# info.net
KiCad netlist of a schematic drawn in EAGLE
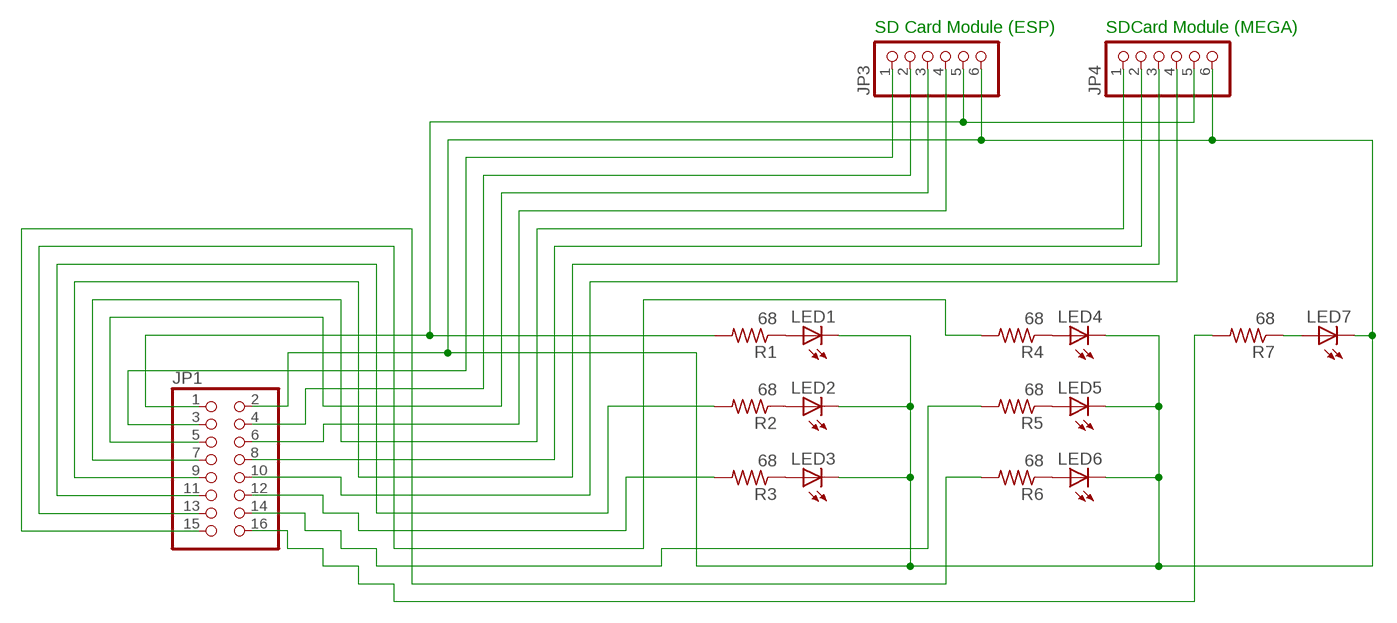
[diagram p0: schematic, sheet 1]

(export (version "E")
  (design (tool "Eeschema 10.0.6"))
  (components
    (comp (ref "JP1")
      (value "PINHD-2X8/90")
      (footprint "eagle-import:2X08_90")
      (libsource (lib "eagle-import") (part "PINHD-2X8/90"))
    )
    (comp (ref "JP3")
      (value "PINHD-1X6")
      (footprint "eagle-import:1X06")
      (libsource (lib "eagle-import") (part "PINHD-1X6"))
    )
    (comp (ref "JP4")
      (value "PINHD-1X6")
      (footprint "eagle-import:1X06")
      (libsource (lib "eagle-import") (part "PINHD-1X6"))
    )
    (comp (ref "LED1")
      (value "LED3MM")
      (footprint "eagle-import:LED3MM")
      (libsource (lib "eagle-import") (part "LED3MM"))
    )
    (comp (ref "LED2")
      (value "LED3MM")
      (footprint "eagle-import:LED3MM")
      (libsource (lib "eagle-import") (part "LED3MM"))
    )
    (comp (ref "LED3")
      (value "LED3MM")
      (footprint "eagle-import:LED3MM")
      (libsource (lib "eagle-import") (part "LED3MM"))
    )
    (comp (ref "LED4")
      (value "LED3MM")
      (footprint "eagle-import:LED3MM")
      (libsource (lib "eagle-import") (part "LED3MM"))
    )
    (comp (ref "LED5")
      (value "LED3MM")
      (footprint "eagle-import:LED3MM")
      (libsource (lib "eagle-import") (part "LED3MM"))
    )
    (comp (ref "LED6")
      (value "LED3MM")
      (footprint "eagle-import:LED3MM")
      (libsource (lib "eagle-import") (part "LED3MM"))
    )
    (comp (ref "LED7")
      (value "LED3MM")
      (footprint "eagle-import:LED3MM")
      (libsource (lib "eagle-import") (part "LED3MM"))
    )
    (comp (ref "R1")
      (value "68")
      (footprint "eagle-import:0204_7")
      (libsource (lib "eagle-import") (part "R-US_0204/7"))
    )
    (comp (ref "R2")
      (value "68")
      (footprint "eagle-import:0204_7")
      (libsource (lib "eagle-import") (part "R-US_0204/7"))
    )
    (comp (ref "R3")
      (value "68")
      (footprint "eagle-import:0204_7")
      (libsource (lib "eagle-import") (part "R-US_0204/7"))
    )
    (comp (ref "R4")
      (value "68")
      (footprint "eagle-import:0204_7")
      (libsource (lib "eagle-import") (part "R-US_0204/7"))
    )
    (comp (ref "R5")
      (value "68")
      (footprint "eagle-import:0204_7")
      (libsource (lib "eagle-import") (part "R-US_0204/7"))
    )
    (comp (ref "R6")
      (value "68")
      (footprint "eagle-import:0204_7")
      (libsource (lib "eagle-import") (part "R-US_0204/7"))
    )
    (comp (ref "R7")
      (value "68")
      (footprint "eagle-import:0204_7")
      (libsource (lib "eagle-import") (part "R-US_0204/7"))
    )
  )
  (nets
    (net (code "1") (name "Net-(JP1-Pad1)") (class "Default")
      (node (ref "JP1") (pin "1") (pinfunction "1_1") (pintype "passive"))
      (node (ref "JP3") (pin "5") (pinfunction "5_5") (pintype "passive"))
      (node (ref "JP4") (pin "5") (pinfunction "5_5") (pintype "passive"))
      (node (ref "R1") (pin "2") (pinfunction "2_2") (pintype "passive"))
    )
    (net (code "2") (name "Net-(JP1-Pad3)") (class "Default")
      (node (ref "JP1") (pin "3") (pinfunction "3_3") (pintype "passive"))
      (node (ref "JP3") (pin "1") (pinfunction "1_1") (pintype "passive"))
    )
    (net (code "3") (name "Net-(JP1-Pad4)") (class "Default")
      (node (ref "JP1") (pin "4") (pinfunction "4_4") (pintype "passive"))
      (node (ref "JP3") (pin "2") (pinfunction "2_2") (pintype "passive"))
    )
    (net (code "4") (name "Net-(JP1-Pad5)") (class "Default")
      (node (ref "JP1") (pin "5") (pinfunction "5_5") (pintype "passive"))
      (node (ref "JP3") (pin "3") (pinfunction "3_3") (pintype "passive"))
    )
    (net (code "5") (name "Net-(JP1-Pad6)") (class "Default")
      (node (ref "JP1") (pin "6") (pinfunction "6_6") (pintype "passive"))
      (node (ref "JP3") (pin "4") (pinfunction "4_4") (pintype "passive"))
    )
    (net (code "6") (name "Net-(JP1-Pad7)") (class "Default")
      (node (ref "JP1") (pin "7") (pinfunction "7_7") (pintype "passive"))
      (node (ref "JP4") (pin "1") (pinfunction "1_1") (pintype "passive"))
    )
    (net (code "7") (name "Net-(JP1-Pad8)") (class "Default")
      (node (ref "JP1") (pin "8") (pinfunction "8_8") (pintype "passive"))
      (node (ref "JP4") (pin "2") (pinfunction "2_2") (pintype "passive"))
    )
    (net (code "8") (name "Net-(JP1-Pad9)") (class "Default")
      (node (ref "JP1") (pin "9") (pinfunction "9_9") (pintype "passive"))
      (node (ref "JP4") (pin "3") (pinfunction "3_3") (pintype "passive"))
    )
    (net (code "9") (name "Net-(JP1-Pad10)") (class "Default")
      (node (ref "JP1") (pin "10") (pinfunction "10_10") (pintype "passive"))
      (node (ref "JP4") (pin "4") (pinfunction "4_4") (pintype "passive"))
    )
    (net (code "10") (name "Net-(JP1-Pad11)") (class "Default")
      (node (ref "JP1") (pin "11") (pinfunction "11_11") (pintype "passive"))
      (node (ref "R2") (pin "2") (pinfunction "2_2") (pintype "passive"))
    )
    (net (code "11") (name "Net-(JP1-Pad12)") (class "Default")
      (node (ref "JP1") (pin "12") (pinfunction "12_12") (pintype "passive"))
      (node (ref "R3") (pin "2") (pinfunction "2_2") (pintype "passive"))
    )
    (net (code "12") (name "Net-(JP1-Pad13)") (class "Default")
      (node (ref "JP1") (pin "13") (pinfunction "13_13") (pintype "passive"))
      (node (ref "R4") (pin "2") (pinfunction "2_2") (pintype "passive"))
    )
    (net (code "13") (name "Net-(JP1-Pad14)") (class "Default")
      (node (ref "JP1") (pin "14") (pinfunction "14_14") (pintype "passive"))
      (node (ref "R5") (pin "2") (pinfunction "2_2") (pintype "passive"))
    )
    (net (code "14") (name "Net-(JP1-Pad15)") (class "Default")
      (node (ref "JP1") (pin "15") (pinfunction "15_15") (pintype "passive"))
      (node (ref "R6") (pin "2") (pinfunction "2_2") (pintype "passive"))
    )
    (net (code "15") (name "Net-(JP1-Pad16)") (class "Default")
      (node (ref "JP1") (pin "16") (pinfunction "16_16") (pintype "passive"))
      (node (ref "R7") (pin "2") (pinfunction "2_2") (pintype "passive"))
    )
    (net (code "16") (name "Net-(LED1-C)") (class "Default")
      (node (ref "JP1") (pin "2") (pinfunction "2_2") (pintype "passive"))
      (node (ref "JP3") (pin "6") (pinfunction "6_6") (pintype "passive"))
      (node (ref "JP4") (pin "6") (pinfunction "6_6") (pintype "passive"))
      (node (ref "LED1") (pin "K") (pinfunction "C_K") (pintype "passive"))
      (node (ref "LED2") (pin "K") (pinfunction "C_K") (pintype "passive"))
      (node (ref "LED3") (pin "K") (pinfunction "C_K") (pintype "passive"))
      (node (ref "LED4") (pin "K") (pinfunction "C_K") (pintype "passive"))
      (node (ref "LED5") (pin "K") (pinfunction "C_K") (pintype "passive"))
      (node (ref "LED6") (pin "K") (pinfunction "C_K") (pintype "passive"))
      (node (ref "LED7") (pin "K") (pinfunction "C_K") (pintype "passive"))
    )
    (net (code "17") (name "Net-(LED1-PadA)") (class "Default")
      (node (ref "LED1") (pin "A") (pinfunction "A_A") (pintype "passive"))
      (node (ref "R1") (pin "1") (pinfunction "1_1") (pintype "passive"))
    )
    (net (code "18") (name "Net-(LED2-PadA)") (class "Default")
      (node (ref "LED2") (pin "A") (pinfunction "A_A") (pintype "passive"))
      (node (ref "R2") (pin "1") (pinfunction "1_1") (pintype "passive"))
    )
    (net (code "19") (name "Net-(LED3-PadA)") (class "Default")
      (node (ref "LED3") (pin "A") (pinfunction "A_A") (pintype "passive"))
      (node (ref "R3") (pin "1") (pinfunction "1_1") (pintype "passive"))
    )
    (net (code "20") (name "Net-(LED4-PadA)") (class "Default")
      (node (ref "LED4") (pin "A") (pinfunction "A_A") (pintype "passive"))
      (node (ref "R4") (pin "1") (pinfunction "1_1") (pintype "passive"))
    )
    (net (code "21") (name "Net-(LED5-PadA)") (class "Default")
      (node (ref "LED5") (pin "A") (pinfunction "A_A") (pintype "passive"))
      (node (ref "R5") (pin "1") (pinfunction "1_1") (pintype "passive"))
    )
    (net (code "22") (name "Net-(LED6-PadA)") (class "Default")
      (node (ref "LED6") (pin "A") (pinfunction "A_A") (pintype "passive"))
      (node (ref "R6") (pin "1") (pinfunction "1_1") (pintype "passive"))
    )
    (net (code "23") (name "Net-(LED7-PadA)") (class "Default")
      (node (ref "LED7") (pin "A") (pinfunction "A_A") (pintype "passive"))
      (node (ref "R7") (pin "1") (pinfunction "1_1") (pintype "passive"))
    )
  )
)
